# GDEnvSensorNode_1_4d.net
KiCad netlist of a schematic drawn in EAGLE
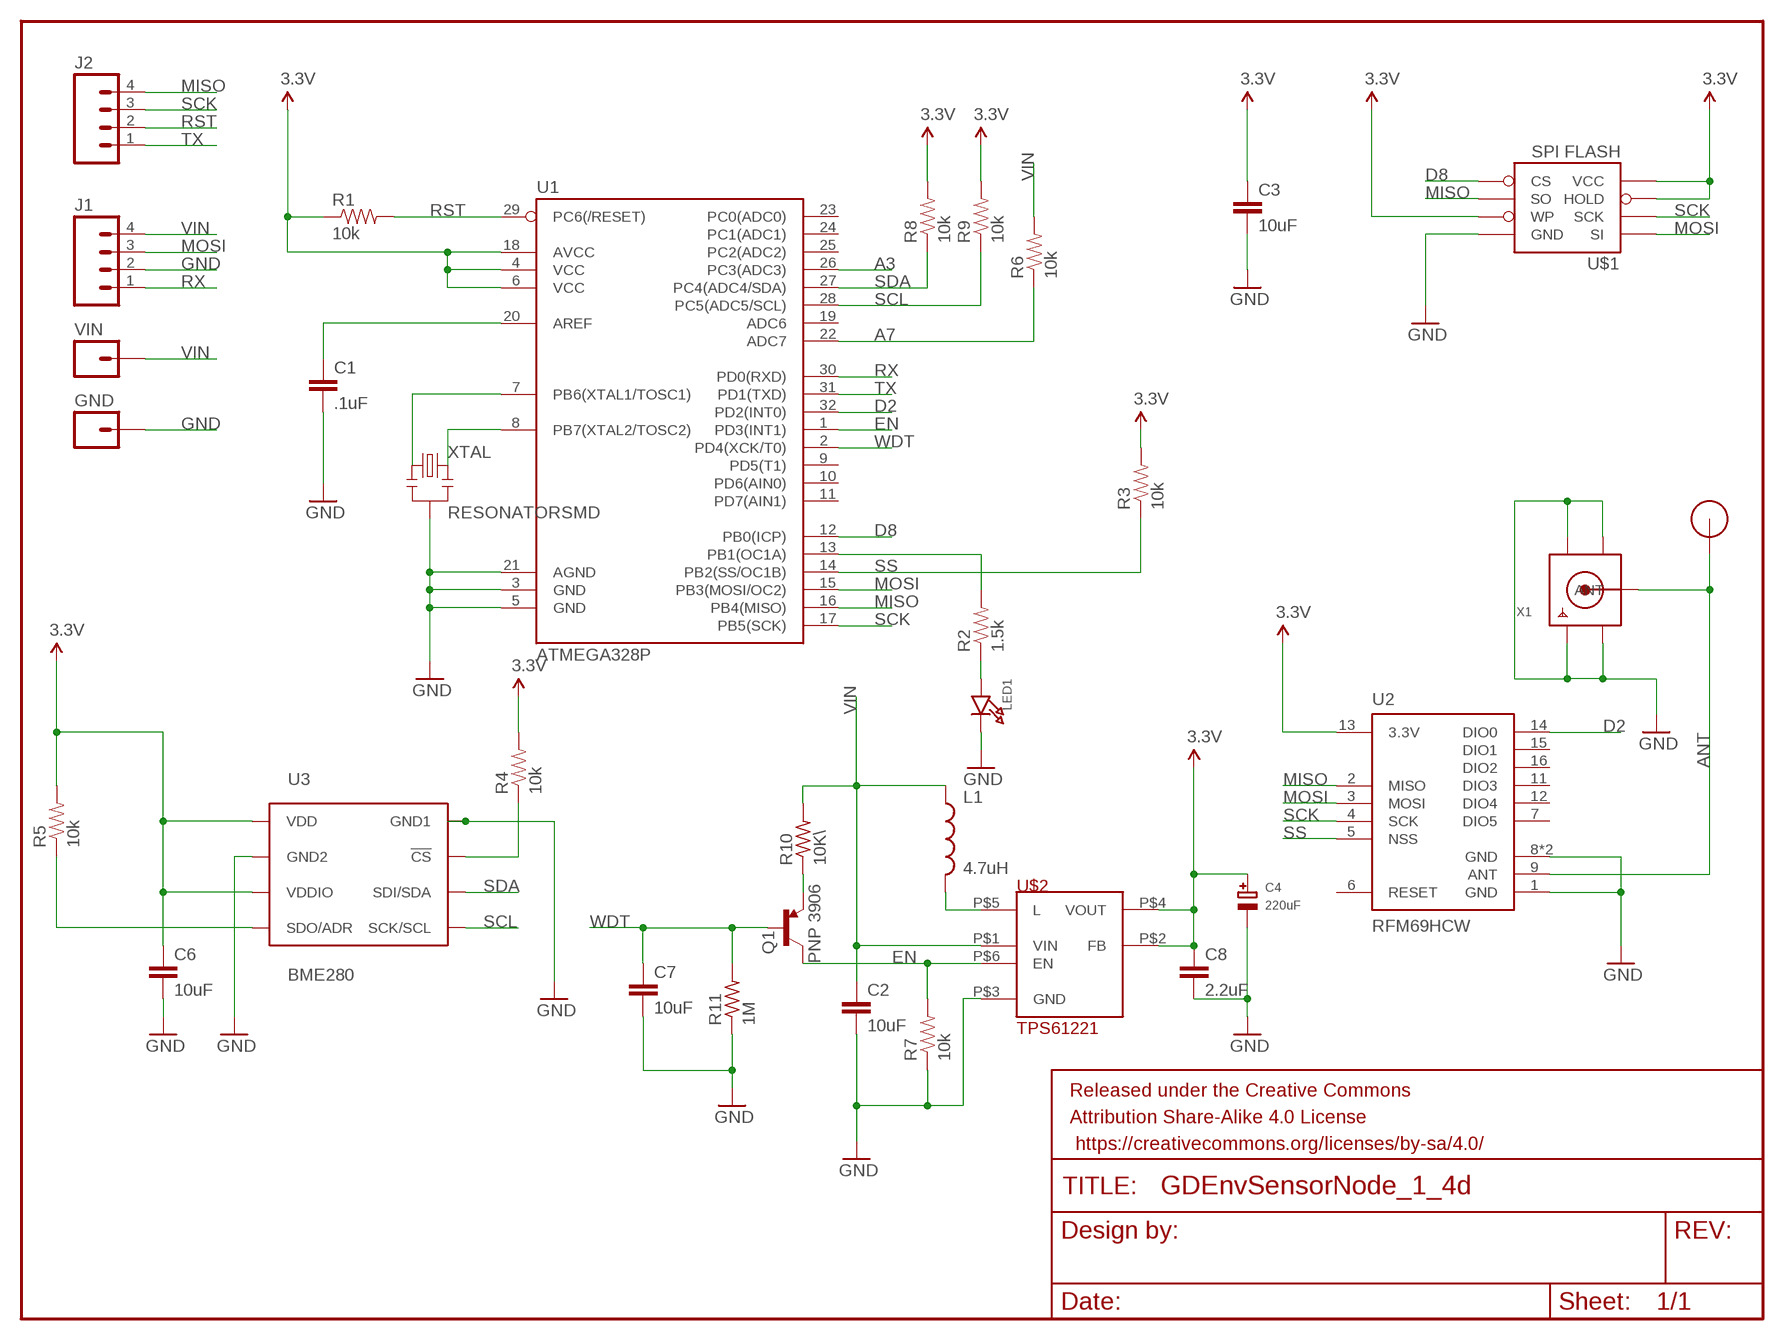
[diagram p0: schematic, sheet 1]

(export (version "E")
  (design (tool "Eeschema 10.0.6"))
  (components
    (comp (ref "C1")
      (value ".1uF")
      (footprint "eagle-import:0805")
      (libsource (lib "eagle-import") (part "CAP0805"))
    )
    (comp (ref "C2")
      (value "10uF")
      (footprint "eagle-import:0805")
      (libsource (lib "eagle-import") (part "CAP0805"))
    )
    (comp (ref "C3")
      (value "10uF")
      (footprint "eagle-import:0805")
      (libsource (lib "eagle-import") (part "CAP0805"))
    )
    (comp (ref "C4")
      (value "220uF")
      (footprint "eagle-import:EIA3528-21_B-R")
      (libsource (lib "eagle-import") (part "CAP_TANTALUMB/3528_REFLOW"))
    )
    (comp (ref "C6")
      (value "10uF")
      (footprint "eagle-import:0805")
      (libsource (lib "eagle-import") (part "CAP0805"))
    )
    (comp (ref "C7")
      (value "10uF")
      (footprint "eagle-import:0805")
      (libsource (lib "eagle-import") (part "CAP0805"))
    )
    (comp (ref "C8")
      (value "2.2uF")
      (footprint "eagle-import:0805")
      (libsource (lib "eagle-import") (part "CAP0805"))
    )
    (comp (ref "FRAME1")
      (value "FRAME-LETTER")
      (footprint "eagle-import:CREATIVE_COMMONS")
      (libsource (lib "eagle-import") (part "FRAME-LETTER"))
    )
    (comp (ref "GND")
      (value "M01PTH_2MM")
      (footprint "eagle-import:1X01_2MM")
      (libsource (lib "eagle-import") (part "M01PTH_2MM"))
    )
    (comp (ref "J1")
      (value "M04PTH")
      (footprint "eagle-import:1X04")
      (libsource (lib "eagle-import") (part "M04PTH"))
    )
    (comp (ref "J2")
      (value "M04PTH")
      (footprint "eagle-import:1X04")
      (libsource (lib "eagle-import") (part "M04PTH"))
    )
    (comp (ref "L1")
      (value "4.7uH")
      (footprint "eagle-import:1210")
      (libsource (lib "eagle-import") (part "INDUCTOR1210"))
    )
    (comp (ref "LED1")
      (value "LED0805")
      (footprint "eagle-import:CHIPLED_0805")
      (libsource (lib "eagle-import") (part "LED0805"))
    )
    (comp (ref "Q1")
      (value "PNP 3906")
      (footprint "eagle-import:SOT23-3")
      (libsource (lib "eagle-import") (part "TRANSISTOR_PNPPMBT3906"))
    )
    (comp (ref "R1")
      (value "10k")
      (footprint "eagle-import:0805")
      (libsource (lib "eagle-import") (part "RESISTOR0805-RES"))
    )
    (comp (ref "R2")
      (value "1.5k")
      (footprint "eagle-import:0805")
      (libsource (lib "eagle-import") (part "RESISTOR0805-RES"))
    )
    (comp (ref "R3")
      (value "10k")
      (footprint "eagle-import:0805")
      (libsource (lib "eagle-import") (part "RESISTOR0805-RES"))
    )
    (comp (ref "R4")
      (value "10k")
      (footprint "eagle-import:0805")
      (libsource (lib "eagle-import") (part "RESISTOR0805-RES"))
    )
    (comp (ref "R5")
      (value "10k")
      (footprint "eagle-import:0805")
      (libsource (lib "eagle-import") (part "RESISTOR0805-RES"))
    )
    (comp (ref "R6")
      (value "10k")
      (footprint "eagle-import:0805")
      (libsource (lib "eagle-import") (part "RESISTOR0805-RES"))
    )
    (comp (ref "R7")
      (value "10k")
      (footprint "eagle-import:0805")
      (libsource (lib "eagle-import") (part "RESISTOR0805-RES"))
    )
    (comp (ref "R8")
      (value "10k")
      (footprint "eagle-import:0805")
      (libsource (lib "eagle-import") (part "RESISTOR0805-RES"))
    )
    (comp (ref "R9")
      (value "10k")
      (footprint "eagle-import:0805")
      (libsource (lib "eagle-import") (part "RESISTOR0805-RES"))
    )
    (comp (ref "R10")
      (value "10K\\")
      (footprint "eagle-import:R0805")
      (libsource (lib "eagle-import") (part "R-US_R0805"))
    )
    (comp (ref "R11")
      (value "1M")
      (footprint "eagle-import:R0805")
      (libsource (lib "eagle-import") (part "R-US_R0805"))
    )
    (comp (ref "U$1")
      (value "SPI FLASH")
      (footprint "eagle-import:SO08")
      (libsource (lib "eagle-import") (part "AT25F512BJEDEC_3.9MM"))
    )
    (comp (ref "U$2")
      (value "TPS61221")
      (footprint "eagle-import:TPS61221")
      (fields (field (name "MF") "Texas Instruments"))
      (libsource (lib "eagle-import") (part "TPS61221"))
    )
    (comp (ref "U$4")
      (value "RFM12B_ANTENNA")
      (footprint "eagle-import:RFM12B-ANTENNA")
      (libsource (lib "eagle-import") (part "RFM12B_ANTENNA"))
    )
    (comp (ref "U1")
      (value "ATMEGA328P")
      (footprint "eagle-import:TQFP32-08")
      (libsource (lib "eagle-import") (part "ATMEGA328P_TQFP"))
    )
    (comp (ref "U2")
      (value "RFM69HCW")
      (footprint "eagle-import:RFM69HCW-XXXS2")
      (libsource (lib "eagle-import") (part "RFM69HCW"))
    )
    (comp (ref "U3")
      (value "BME280")
      (footprint "eagle-import:BME280_LGA")
      (libsource (lib "eagle-import") (part "BME280"))
    )
    (comp (ref "VIN")
      (value "M01PTH_2MM")
      (footprint "eagle-import:1X01_2MM")
      (libsource (lib "eagle-import") (part "M01PTH_2MM"))
    )
    (comp (ref "X1")
      (value "SMACONNECTOR_EDGE_UFL")
      (footprint "eagle-import:SMA_EDGELAUNCH_UFL")
      (libsource (lib "eagle-import") (part "SMACONNECTOR_EDGE_UFL"))
    )
    (comp (ref "XTAL")
      (value "RESONATORSMD")
      (footprint "eagle-import:RESONATOR-SMD")
      (libsource (lib "eagle-import") (part "RESONATORSMD"))
    )
  )
  (nets
    (net (code "1") (name "/A3") (class "Default")
      (node (ref "U1") (pin "26") (pinfunction "PC3(ADC3)_26") (pintype "bidirectional"))
    )
    (net (code "2") (name "/A7") (class "Default")
      (node (ref "R6") (pin "1") (pinfunction "1_1") (pintype "passive"))
      (node (ref "U1") (pin "22") (pinfunction "ADC7_22") (pintype "bidirectional"))
    )
    (net (code "3") (name "/ANT") (class "Default")
      (node (ref "U$4") (pin "P$1") (pinfunction "1_P$1") (pintype "bidirectional"))
      (node (ref "U2") (pin "9") (pinfunction "ANT_9") (pintype "passive"))
      (node (ref "X1") (pin "P") (pinfunction "ANT_P") (pintype "bidirectional"))
    )
    (net (code "4") (name "/D2") (class "Default")
      (node (ref "U1") (pin "32") (pinfunction "PD2(INT0)_32") (pintype "bidirectional"))
      (node (ref "U2") (pin "14") (pinfunction "DIO0_14") (pintype "bidirectional"))
    )
    (net (code "5") (name "/D8") (class "Default")
      (node (ref "U$1") (pin "1_CS") (pinfunction "CS_1_CS") (pintype "bidirectional"))
      (node (ref "U1") (pin "12") (pinfunction "PB0(ICP)_12") (pintype "bidirectional"))
    )
    (net (code "6") (name "/EN") (class "Default")
      (node (ref "Q1") (pin "3") (pinfunction "C_3") (pintype "passive"))
      (node (ref "R7") (pin "2") (pinfunction "2_2") (pintype "passive"))
      (node (ref "U$2") (pin "P$6") (pinfunction "EN_P$6") (pintype "bidirectional"))
      (node (ref "U1") (pin "1") (pinfunction "PD3(INT1)_1") (pintype "bidirectional"))
    )
    (net (code "7") (name "/MISO") (class "Default")
      (node (ref "J2") (pin "4") (pinfunction "4_4") (pintype "passive"))
      (node (ref "U$1") (pin "2_SO") (pinfunction "SO_2_SO") (pintype "bidirectional"))
      (node (ref "U1") (pin "16") (pinfunction "PB4(MISO)_16") (pintype "bidirectional"))
      (node (ref "U2") (pin "2") (pinfunction "MISO_2") (pintype "bidirectional"))
    )
    (net (code "8") (name "/MOSI") (class "Default")
      (node (ref "J1") (pin "3") (pinfunction "3_3") (pintype "passive"))
      (node (ref "U$1") (pin "5_SI") (pinfunction "SI_5_SI") (pintype "bidirectional"))
      (node (ref "U1") (pin "15") (pinfunction "PB3(MOSI/OC2)_15") (pintype "bidirectional"))
      (node (ref "U2") (pin "3") (pinfunction "MOSI_3") (pintype "input"))
    )
    (net (code "9") (name "/RST") (class "Default")
      (node (ref "J2") (pin "2") (pinfunction "2_2") (pintype "passive"))
      (node (ref "R1") (pin "2") (pinfunction "2_2") (pintype "passive"))
      (node (ref "U1") (pin "29") (pinfunction "PC6(/RESET)_29") (pintype "bidirectional"))
    )
    (net (code "10") (name "/RX") (class "Default")
      (node (ref "J1") (pin "1") (pinfunction "1_1") (pintype "passive"))
      (node (ref "U1") (pin "30") (pinfunction "PD0(RXD)_30") (pintype "bidirectional"))
    )
    (net (code "11") (name "/SCK") (class "Default")
      (node (ref "J2") (pin "3") (pinfunction "3_3") (pintype "passive"))
      (node (ref "U$1") (pin "6_SCK") (pinfunction "SCK_6_SCK") (pintype "bidirectional"))
      (node (ref "U1") (pin "17") (pinfunction "PB5(SCK)_17") (pintype "bidirectional"))
      (node (ref "U2") (pin "4") (pinfunction "SCK_4") (pintype "input"))
    )
    (net (code "12") (name "/SCL") (class "Default")
      (node (ref "R9") (pin "1") (pinfunction "1_1") (pintype "passive"))
      (node (ref "U1") (pin "28") (pinfunction "PC5(ADC5/SCL)_28") (pintype "bidirectional"))
      (node (ref "U3") (pin "P$4") (pinfunction "SCK/SCL_P$4") (pintype "bidirectional"))
    )
    (net (code "13") (name "/SDA") (class "Default")
      (node (ref "R8") (pin "1") (pinfunction "1_1") (pintype "passive"))
      (node (ref "U1") (pin "27") (pinfunction "PC4(ADC4/SDA)_27") (pintype "bidirectional"))
      (node (ref "U3") (pin "P$3") (pinfunction "SDI/SDA_P$3") (pintype "bidirectional"))
    )
    (net (code "14") (name "/SS") (class "Default")
      (node (ref "R3") (pin "1") (pinfunction "1_1") (pintype "passive"))
      (node (ref "U1") (pin "14") (pinfunction "PB2(SS/OC1B)_14") (pintype "bidirectional"))
      (node (ref "U2") (pin "5") (pinfunction "NSS_5") (pintype "input"))
    )
    (net (code "15") (name "/TX") (class "Default")
      (node (ref "J2") (pin "1") (pinfunction "1_1") (pintype "passive"))
      (node (ref "U1") (pin "31") (pinfunction "PD1(TXD)_31") (pintype "bidirectional"))
    )
    (net (code "16") (name "/VIN") (class "Default")
      (node (ref "C2") (pin "1") (pinfunction "1_1") (pintype "passive"))
      (node (ref "J1") (pin "4") (pinfunction "4_4") (pintype "passive"))
      (node (ref "L1") (pin "1") (pinfunction "1_1") (pintype "passive"))
      (node (ref "R10") (pin "2") (pinfunction "2_2") (pintype "passive"))
      (node (ref "R6") (pin "2") (pinfunction "2_2") (pintype "passive"))
      (node (ref "U$2") (pin "P$1") (pinfunction "VIN_P$1") (pintype "bidirectional"))
      (node (ref "VIN") (pin "1") (pinfunction "1_1") (pintype "passive"))
    )
    (net (code "17") (name "/WDT") (class "Default")
      (node (ref "C7") (pin "1") (pinfunction "1_1") (pintype "passive"))
      (node (ref "Q1") (pin "1") (pinfunction "B_1") (pintype "passive"))
      (node (ref "R11") (pin "2") (pinfunction "2_2") (pintype "passive"))
      (node (ref "U1") (pin "2") (pinfunction "PD4(XCK/T0)_2") (pintype "bidirectional"))
    )
    (net (code "18") (name "3.3V") (class "Default")
      (node (ref "C3") (pin "1") (pinfunction "1_1") (pintype "passive"))
      (node (ref "C4") (pin "+") (pinfunction "+_+") (pintype "passive"))
      (node (ref "C6") (pin "1") (pinfunction "1_1") (pintype "passive"))
      (node (ref "C8") (pin "1") (pinfunction "1_1") (pintype "passive"))
      (node (ref "R1") (pin "1") (pinfunction "1_1") (pintype "passive"))
      (node (ref "R3") (pin "2") (pinfunction "2_2") (pintype "passive"))
      (node (ref "R4") (pin "2") (pinfunction "2_2") (pintype "passive"))
      (node (ref "R5") (pin "2") (pinfunction "2_2") (pintype "passive"))
      (node (ref "R8") (pin "2") (pinfunction "2_2") (pintype "passive"))
      (node (ref "R9") (pin "2") (pinfunction "2_2") (pintype "passive"))
      (node (ref "U$1") (pin "3_WP") (pinfunction "WP_3_WP") (pintype "bidirectional"))
      (node (ref "U$1") (pin "7_HOLD") (pinfunction "HOLD_7_HOLD") (pintype "bidirectional"))
      (node (ref "U$1") (pin "8_VCC") (pinfunction "VCC_8_VCC") (pintype "bidirectional"))
      (node (ref "U$2") (pin "P$2") (pinfunction "FB_P$2") (pintype "bidirectional"))
      (node (ref "U$2") (pin "P$4") (pinfunction "VOUT_P$4") (pintype "bidirectional"))
      (node (ref "U1") (pin "18") (pinfunction "AVCC_18") (pintype "bidirectional"))
      (node (ref "U1") (pin "4") (pinfunction "VCC_4") (pintype "bidirectional"))
      (node (ref "U1") (pin "6") (pinfunction "VCC_6") (pintype "bidirectional"))
      (node (ref "U2") (pin "13") (pinfunction "3.3V_13") (pintype "power_in"))
      (node (ref "U3") (pin "P$6") (pinfunction "VDDIO_P$6") (pintype "bidirectional"))
      (node (ref "U3") (pin "P$8") (pinfunction "VDD_P$8") (pintype "bidirectional"))
    )
    (net (code "19") (name "GND") (class "Default")
      (node (ref "C1") (pin "2") (pinfunction "2_2") (pintype "passive"))
      (node (ref "C2") (pin "2") (pinfunction "2_2") (pintype "passive"))
      (node (ref "C3") (pin "2") (pinfunction "2_2") (pintype "passive"))
      (node (ref "C4") (pin "-") (pinfunction "-_-") (pintype "passive"))
      (node (ref "C6") (pin "2") (pinfunction "2_2") (pintype "passive"))
      (node (ref "C7") (pin "2") (pinfunction "2_2") (pintype "passive"))
      (node (ref "C8") (pin "2") (pinfunction "2_2") (pintype "passive"))
      (node (ref "GND") (pin "1") (pinfunction "1_1") (pintype "passive"))
      (node (ref "J1") (pin "2") (pinfunction "2_2") (pintype "passive"))
      (node (ref "LED1") (pin "C") (pinfunction "C_C") (pintype "passive"))
      (node (ref "R11") (pin "1") (pinfunction "1_1") (pintype "passive"))
      (node (ref "R7") (pin "1") (pinfunction "1_1") (pintype "passive"))
      (node (ref "U$1") (pin "4_GND") (pinfunction "GND_4_GND") (pintype "bidirectional"))
      (node (ref "U$2") (pin "P$3") (pinfunction "GND_P$3") (pintype "bidirectional"))
      (node (ref "U1") (pin "21") (pinfunction "AGND_21") (pintype "bidirectional"))
      (node (ref "U1") (pin "3") (pinfunction "GND_3") (pintype "bidirectional"))
      (node (ref "U1") (pin "5") (pinfunction "GND_5") (pintype "bidirectional"))
      (node (ref "U2") (pin "1") (pinfunction "GND_1") (pintype "power_in"))
      (node (ref "U2") (pin "10") (pinfunction "GND_10") (pintype "power_in"))
      (node (ref "U2") (pin "8") (pinfunction "GND_8") (pintype "power_in"))
      (node (ref "U3") (pin "P$1") (pinfunction "GND1_P$1") (pintype "bidirectional"))
      (node (ref "U3") (pin "P$7") (pinfunction "GND2_P$7") (pintype "bidirectional"))
      (node (ref "X1") (pin "GND@1") (pinfunction "GND1_GND@1") (pintype "power_in"))
      (node (ref "X1") (pin "GND@2") (pinfunction "GND2_GND@2") (pintype "power_in"))
      (node (ref "X1") (pin "GND@3") (pinfunction "GND3_GND@3") (pintype "power_in"))
      (node (ref "X1") (pin "GND@4") (pinfunction "GND4_GND@4") (pintype "power_in"))
      (node (ref "XTAL") (pin "2") (pinfunction "2_2") (pintype "passive"))
    )
    (net (code "20") (name "Net-(LED1-PadA)") (class "Default")
      (node (ref "LED1") (pin "A") (pinfunction "A_A") (pintype "passive"))
      (node (ref "R2") (pin "1") (pinfunction "1_1") (pintype "passive"))
    )
    (net (code "21") (name "Net-(Q1-E)") (class "Default")
      (node (ref "Q1") (pin "2") (pinfunction "E_2") (pintype "passive"))
      (node (ref "R10") (pin "1") (pinfunction "1_1") (pintype "passive"))
    )
    (net (code "22") (name "Net-(U$2-L)") (class "Default")
      (node (ref "L1") (pin "2") (pinfunction "2_2") (pintype "passive"))
      (node (ref "U$2") (pin "P$5") (pinfunction "L_P$5") (pintype "bidirectional"))
    )
    (net (code "23") (name "Net-(U1-AREF)") (class "Default")
      (node (ref "C1") (pin "1") (pinfunction "1_1") (pintype "passive"))
      (node (ref "U1") (pin "20") (pinfunction "AREF_20") (pintype "bidirectional"))
    )
    (net (code "24") (name "Net-(U1-PB1(OC1A))") (class "Default")
      (node (ref "R2") (pin "2") (pinfunction "2_2") (pintype "passive"))
      (node (ref "U1") (pin "13") (pinfunction "PB1(OC1A)_13") (pintype "bidirectional"))
    )
    (net (code "25") (name "Net-(U1-PB6(XTAL1{slash}TOSC1))") (class "Default")
      (node (ref "U1") (pin "7") (pinfunction "PB6(XTAL1/TOSC1)_7") (pintype "bidirectional"))
      (node (ref "XTAL") (pin "1") (pinfunction "1_1") (pintype "passive"))
    )
    (net (code "26") (name "Net-(U1-PB7(XTAL2{slash}TOSC2))") (class "Default")
      (node (ref "U1") (pin "8") (pinfunction "PB7(XTAL2/TOSC2)_8") (pintype "bidirectional"))
      (node (ref "XTAL") (pin "3") (pinfunction "3_3") (pintype "passive"))
    )
    (net (code "27") (name "Net-(U3-SDO{slash}ADR)") (class "Default")
      (node (ref "R5") (pin "1") (pinfunction "1_1") (pintype "passive"))
      (node (ref "U3") (pin "P$5") (pinfunction "SDO/ADR_P$5") (pintype "bidirectional"))
    )
    (net (code "28") (name "Net-(U3-~{CS})") (class "Default")
      (node (ref "R4") (pin "1") (pinfunction "1_1") (pintype "passive"))
      (node (ref "U3") (pin "P$2") (pinfunction "~{CS}_P$2") (pintype "bidirectional"))
    )
    (net (code "29") (name "unconnected-(U1-ADC6-Pad19)") (class "Default")
      (node (ref "U1") (pin "19") (pinfunction "ADC6_19") (pintype "bidirectional"))
    )
    (net (code "30") (name "unconnected-(U1-PC0(ADC0)-Pad23)") (class "Default")
      (node (ref "U1") (pin "23") (pinfunction "PC0(ADC0)_23") (pintype "bidirectional"))
    )
    (net (code "31") (name "unconnected-(U1-PC1(ADC1)-Pad24)") (class "Default")
      (node (ref "U1") (pin "24") (pinfunction "PC1(ADC1)_24") (pintype "bidirectional"))
    )
    (net (code "32") (name "unconnected-(U1-PC2(ADC2)-Pad25)") (class "Default")
      (node (ref "U1") (pin "25") (pinfunction "PC2(ADC2)_25") (pintype "bidirectional"))
    )
    (net (code "33") (name "unconnected-(U1-PD5(T1)-Pad9)") (class "Default")
      (node (ref "U1") (pin "9") (pinfunction "PD5(T1)_9") (pintype "bidirectional"))
    )
    (net (code "34") (name "unconnected-(U1-PD6(AIN0)-Pad10)") (class "Default")
      (node (ref "U1") (pin "10") (pinfunction "PD6(AIN0)_10") (pintype "bidirectional"))
    )
    (net (code "35") (name "unconnected-(U1-PD7(AIN1)-Pad11)") (class "Default")
      (node (ref "U1") (pin "11") (pinfunction "PD7(AIN1)_11") (pintype "bidirectional"))
    )
    (net (code "36") (name "unconnected-(U2-DIO1-Pad15)") (class "Default")
      (node (ref "U2") (pin "15") (pinfunction "DIO1_15") (pintype "bidirectional"))
    )
    (net (code "37") (name "unconnected-(U2-DIO2-Pad16)") (class "Default")
      (node (ref "U2") (pin "16") (pinfunction "DIO2_16") (pintype "bidirectional"))
    )
    (net (code "38") (name "unconnected-(U2-DIO3-Pad11)") (class "Default")
      (node (ref "U2") (pin "11") (pinfunction "DIO3_11") (pintype "bidirectional"))
    )
    (net (code "39") (name "unconnected-(U2-DIO4-Pad12)") (class "Default")
      (node (ref "U2") (pin "12") (pinfunction "DIO4_12") (pintype "bidirectional"))
    )
    (net (code "40") (name "unconnected-(U2-DIO5-Pad7)") (class "Default")
      (node (ref "U2") (pin "7") (pinfunction "DIO5_7") (pintype "bidirectional"))
    )
    (net (code "41") (name "unconnected-(U2-RESET-Pad6)") (class "Default")
      (node (ref "U2") (pin "6") (pinfunction "RESET_6") (pintype "input"))
    )
  )
)
